# ai_firefly.net
KiCad netlist of a schematic drawn in EAGLE
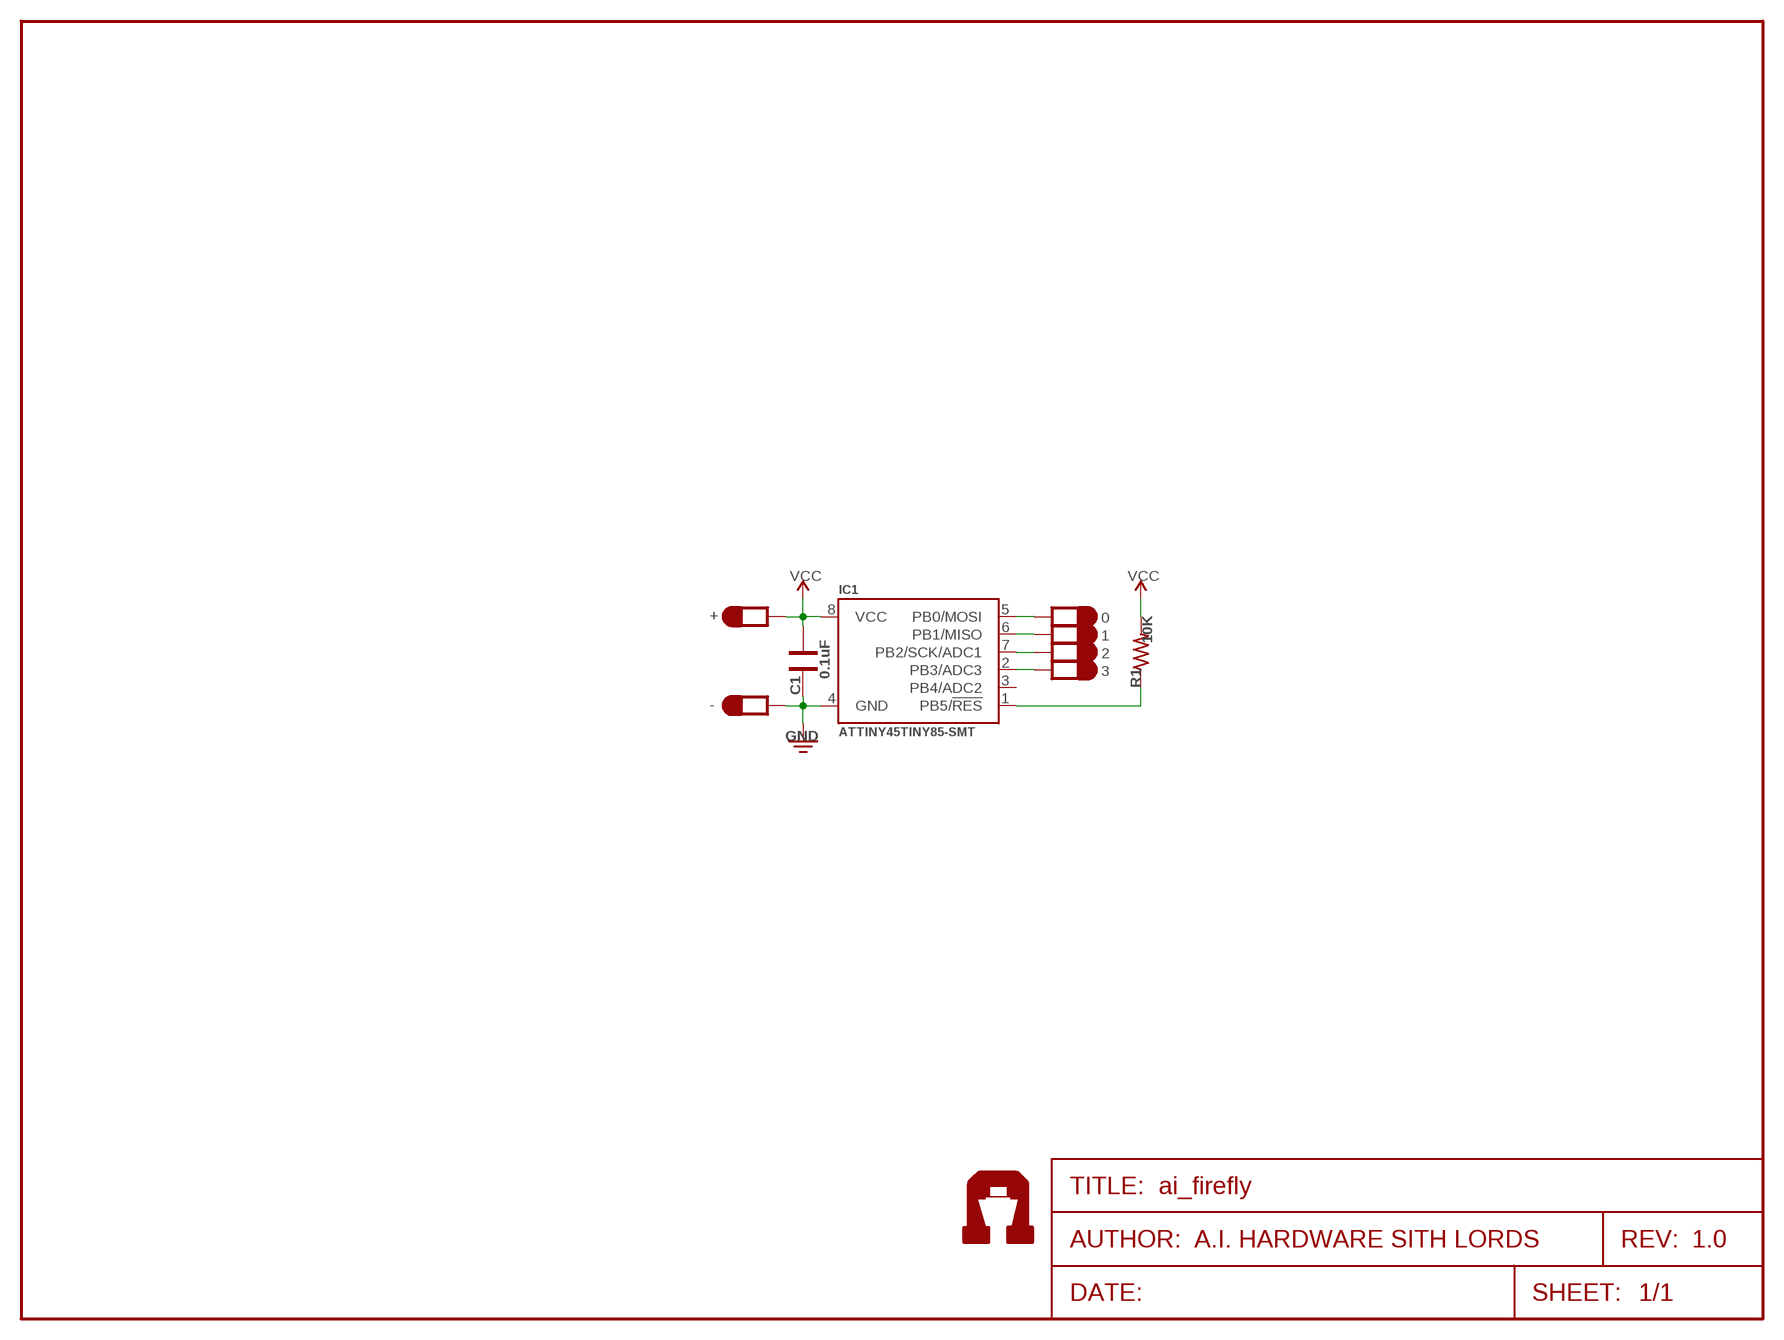
[diagram p0: schematic, sheet 1]

(export (version "E")
  (design (tool "Eeschema 10.0.6"))
  (components
    (comp (ref "+")
      (value "1X01-PETAL")
      (footprint "eagle-import:1X01-PETAL")
      (libsource (lib "eagle-import") (part "1X01-PETAL"))
    )
    (comp (ref "-")
      (value "1X01-PETAL")
      (footprint "eagle-import:1X01-PETAL")
      (libsource (lib "eagle-import") (part "1X01-PETAL"))
    )
    (comp (ref "0")
      (value "1X01-PETAL")
      (footprint "eagle-import:1X01-PETAL")
      (libsource (lib "eagle-import") (part "1X01-PETAL"))
    )
    (comp (ref "1")
      (value "1X01-PETAL")
      (footprint "eagle-import:1X01-PETAL")
      (libsource (lib "eagle-import") (part "1X01-PETAL"))
    )
    (comp (ref "2")
      (value "1X01-PETAL")
      (footprint "eagle-import:1X01-PETAL")
      (libsource (lib "eagle-import") (part "1X01-PETAL"))
    )
    (comp (ref "3")
      (value "1X01-PETAL")
      (footprint "eagle-import:1X01-PETAL")
      (libsource (lib "eagle-import") (part "1X01-PETAL"))
    )
    (comp (ref "C1")
      (value "0.1uF")
      (footprint "eagle-import:CAP-0603")
      (libsource (lib "eagle-import") (part "CAP0603"))
    )
    (comp (ref "IC1")
      (value "ATTINY45TINY85-SMT")
      (footprint "eagle-import:S008-EIAJ")
      (libsource (lib "eagle-import") (part "ATTINY45TINY85-SMT"))
    )
    (comp (ref "R1")
      (value "10K")
      (footprint "eagle-import:RES-0603")
      (libsource (lib "eagle-import") (part "RES0603"))
    )
    (comp (ref "U$9")
      (value "AI-LOGOXS")
      (footprint "eagle-import:AI-LOGO-XS")
      (libsource (lib "eagle-import") (part "AI-LOGOXS"))
    )
  )
  (nets
    (net (code "1") (name "GND") (class "Default")
      (node (ref "-") (pin "1") (pinfunction "1_1") (pintype "bidirectional"))
      (node (ref "C1") (pin "2") (pinfunction "2_2") (pintype "passive"))
      (node (ref "IC1") (pin "4") (pinfunction "GND_4") (pintype "bidirectional"))
    )
    (net (code "2") (name "Net-(IC1-PB0{slash}MOSI)") (class "Default")
      (node (ref "0") (pin "1") (pinfunction "1_1") (pintype "bidirectional"))
      (node (ref "IC1") (pin "5") (pinfunction "PB0/MOSI_5") (pintype "bidirectional"))
    )
    (net (code "3") (name "Net-(IC1-PB1{slash}MISO)") (class "Default")
      (node (ref "1") (pin "1") (pinfunction "1_1") (pintype "bidirectional"))
      (node (ref "IC1") (pin "6") (pinfunction "PB1/MISO_6") (pintype "bidirectional"))
    )
    (net (code "4") (name "Net-(IC1-PB2{slash}SCK{slash}ADC1)") (class "Default")
      (node (ref "2") (pin "1") (pinfunction "1_1") (pintype "bidirectional"))
      (node (ref "IC1") (pin "7") (pinfunction "PB2/SCK/ADC1_7") (pintype "bidirectional"))
    )
    (net (code "5") (name "Net-(IC1-PB3{slash}ADC3)") (class "Default")
      (node (ref "3") (pin "1") (pinfunction "1_1") (pintype "bidirectional"))
      (node (ref "IC1") (pin "2") (pinfunction "PB3/ADC3_2") (pintype "bidirectional"))
    )
    (net (code "6") (name "Net-(IC1-PB5{slash}~{RES})") (class "Default")
      (node (ref "IC1") (pin "1") (pinfunction "PB5/~{RES}_1") (pintype "bidirectional"))
      (node (ref "R1") (pin "1") (pinfunction "1_1") (pintype "passive"))
    )
    (net (code "7") (name "VCC") (class "Default")
      (node (ref "+") (pin "1") (pinfunction "1_1") (pintype "bidirectional"))
      (node (ref "C1") (pin "1") (pinfunction "1_1") (pintype "passive"))
      (node (ref "IC1") (pin "8") (pinfunction "VCC_8") (pintype "bidirectional"))
      (node (ref "R1") (pin "2") (pinfunction "2_2") (pintype "passive"))
    )
    (net (code "8") (name "unconnected-(IC1-PB4{slash}ADC2-Pad3)") (class "Default")
      (node (ref "IC1") (pin "3") (pinfunction "PB4/ADC2_3") (pintype "bidirectional"))
    )
  )
)
